# Attiny85VUSB.net
KiCad netlist of a schematic drawn in EAGLE
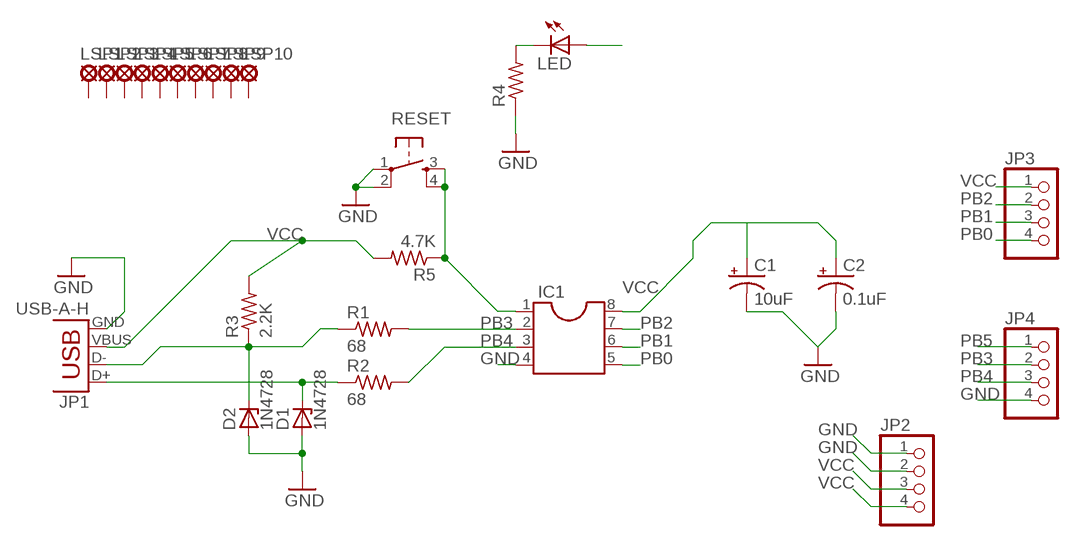
[diagram p0: schematic, sheet 1]

(export (version "E")
  (design (tool "Eeschema 10.0.6"))
  (components
    (comp (ref "C1")
      (value "10uF")
      (footprint "eagle-import:CPOL-RADIAL-100UF-25V")
      (libsource (lib "eagle-import") (part "CAP_POLPTH1"))
    )
    (comp (ref "C2")
      (value "0.1uF")
      (footprint "eagle-import:CPOL-RADIAL-100UF-25V")
      (libsource (lib "eagle-import") (part "CAP_POLPTH1"))
    )
    (comp (ref "D1")
      (value "1N4728")
      (footprint "eagle-import:DO41Z10")
      (libsource (lib "eagle-import") (part "1N4728"))
    )
    (comp (ref "D2")
      (value "1N4728")
      (footprint "eagle-import:DO41Z10")
      (libsource (lib "eagle-import") (part "1N4728"))
    )
    (comp (ref "IC1")
      (value "ATTINY85TESTS")
      (footprint "eagle-import:SOCKET-08")
      (libsource (lib "eagle-import") (part "ATTINY85TESTS"))
    )
    (comp (ref "JP1")
      (value "USB-A-H")
      (footprint "eagle-import:USB-A-H")
      (libsource (lib "eagle-import") (part "USB-A-H"))
    )
    (comp (ref "JP2")
      (value "PINHD-1X4")
      (footprint "eagle-import:1X04")
      (libsource (lib "eagle-import") (part "PINHD-1X4"))
    )
    (comp (ref "JP3")
      (value "PINHD-1X4")
      (footprint "eagle-import:1X04")
      (libsource (lib "eagle-import") (part "PINHD-1X4"))
    )
    (comp (ref "JP4")
      (value "PINHD-1X4")
      (footprint "eagle-import:1X04")
      (libsource (lib "eagle-import") (part "PINHD-1X4"))
    )
    (comp (ref "LED")
      (value "LED5MM")
      (footprint "eagle-import:LED5MM")
      (libsource (lib "eagle-import") (part "LED5MM"))
    )
    (comp (ref "LSP1")
      (value "MCS08")
      (footprint "eagle-import:MCS08")
      (libsource (lib "eagle-import") (part "MCS08"))
    )
    (comp (ref "LSP2")
      (value "MCS08")
      (footprint "eagle-import:MCS08")
      (libsource (lib "eagle-import") (part "MCS08"))
    )
    (comp (ref "LSP3")
      (value "MCS08")
      (footprint "eagle-import:MCS08")
      (libsource (lib "eagle-import") (part "MCS08"))
    )
    (comp (ref "LSP4")
      (value "MCS08")
      (footprint "eagle-import:MCS08")
      (libsource (lib "eagle-import") (part "MCS08"))
    )
    (comp (ref "LSP5")
      (value "MCS08")
      (footprint "eagle-import:MCS08")
      (libsource (lib "eagle-import") (part "MCS08"))
    )
    (comp (ref "LSP6")
      (value "MCS08")
      (footprint "eagle-import:MCS08")
      (libsource (lib "eagle-import") (part "MCS08"))
    )
    (comp (ref "LSP7")
      (value "MCS08")
      (footprint "eagle-import:MCS08")
      (libsource (lib "eagle-import") (part "MCS08"))
    )
    (comp (ref "LSP8")
      (value "MCS08")
      (footprint "eagle-import:MCS08")
      (libsource (lib "eagle-import") (part "MCS08"))
    )
    (comp (ref "LSP9")
      (value "MCS08")
      (footprint "eagle-import:MCS08")
      (libsource (lib "eagle-import") (part "MCS08"))
    )
    (comp (ref "LSP10")
      (value "MCS08")
      (footprint "eagle-import:MCS08")
      (libsource (lib "eagle-import") (part "MCS08"))
    )
    (comp (ref "R1")
      (value "68")
      (footprint "eagle-import:0207_9")
      (libsource (lib "eagle-import") (part "R-US_0207/9"))
    )
    (comp (ref "R2")
      (value "68")
      (footprint "eagle-import:0207_9")
      (libsource (lib "eagle-import") (part "R-US_0207/9"))
    )
    (comp (ref "R3")
      (value "2.2K")
      (footprint "eagle-import:0207_9")
      (libsource (lib "eagle-import") (part "R-US_0207/9"))
    )
    (comp (ref "R4")
      (value "R-US_0207/9")
      (footprint "eagle-import:0207_9")
      (libsource (lib "eagle-import") (part "R-US_0207/9"))
    )
    (comp (ref "R5")
      (value "4.7K")
      (footprint "eagle-import:0207_9")
      (libsource (lib "eagle-import") (part "R-US_0207/9"))
    )
    (comp (ref "RESET")
      (value "TAC_SWITCHPTH")
      (footprint "eagle-import:TACTILE-PTH")
      (libsource (lib "eagle-import") (part "TAC_SWITCHPTH"))
    )
  )
  (nets
    (net (code "1") (name "/PB0") (class "Default")
      (node (ref "IC1") (pin "5") (pinfunction "PB0MOSI_5") (pintype "passive"))
      (node (ref "JP3") (pin "4") (pinfunction "4_4") (pintype "passive"))
    )
    (net (code "2") (name "/PB1") (class "Default")
      (node (ref "IC1") (pin "6") (pinfunction "PB1_MISO_6") (pintype "passive"))
      (node (ref "JP3") (pin "3") (pinfunction "3_3") (pintype "passive"))
      (node (ref "LED") (pin "A") (pinfunction "A_A") (pintype "passive"))
    )
    (net (code "3") (name "/PB2") (class "Default")
      (node (ref "IC1") (pin "7") (pinfunction "PB2SCK_7") (pintype "passive"))
      (node (ref "JP3") (pin "2") (pinfunction "2_2") (pintype "passive"))
    )
    (net (code "4") (name "/PB3") (class "Default")
      (node (ref "IC1") (pin "2") (pinfunction "PB3_CLKI_2") (pintype "passive"))
      (node (ref "JP4") (pin "2") (pinfunction "2_2") (pintype "passive"))
      (node (ref "R1") (pin "2") (pinfunction "2_2") (pintype "passive"))
    )
    (net (code "5") (name "/PB4") (class "Default")
      (node (ref "IC1") (pin "3") (pinfunction "PB4_CLKO_3") (pintype "passive"))
      (node (ref "JP4") (pin "3") (pinfunction "3_3") (pintype "passive"))
      (node (ref "R2") (pin "2") (pinfunction "2_2") (pintype "passive"))
    )
    (net (code "6") (name "/PB5") (class "Default")
      (node (ref "JP4") (pin "1") (pinfunction "1_1") (pintype "passive"))
    )
    (net (code "7") (name "/VCC") (class "Default")
      (node (ref "C1") (pin "1") (pinfunction "+_1") (pintype "passive"))
      (node (ref "C2") (pin "1") (pinfunction "+_1") (pintype "passive"))
      (node (ref "IC1") (pin "8") (pinfunction "VCC_8") (pintype "passive"))
      (node (ref "JP1") (pin "VBUS") (pinfunction "VBUS_VBUS") (pintype "bidirectional"))
      (node (ref "JP2") (pin "3") (pinfunction "3_3") (pintype "passive"))
      (node (ref "JP2") (pin "4") (pinfunction "4_4") (pintype "passive"))
      (node (ref "JP3") (pin "1") (pinfunction "1_1") (pintype "passive"))
      (node (ref "R3") (pin "2") (pinfunction "2_2") (pintype "passive"))
      (node (ref "R5") (pin "2") (pinfunction "2_2") (pintype "passive"))
    )
    (net (code "8") (name "GND") (class "Default")
      (node (ref "C1") (pin "2") (pinfunction "-_2") (pintype "passive"))
      (node (ref "C2") (pin "2") (pinfunction "-_2") (pintype "passive"))
      (node (ref "D1") (pin "A") (pinfunction "A_A") (pintype "passive"))
      (node (ref "D2") (pin "A") (pinfunction "A_A") (pintype "passive"))
      (node (ref "IC1") (pin "4") (pinfunction "GND_4") (pintype "passive"))
      (node (ref "JP1") (pin "GND") (pinfunction "GND_GND") (pintype "bidirectional"))
      (node (ref "JP2") (pin "1") (pinfunction "1_1") (pintype "passive"))
      (node (ref "JP2") (pin "2") (pinfunction "2_2") (pintype "passive"))
      (node (ref "JP4") (pin "4") (pinfunction "4_4") (pintype "passive"))
      (node (ref "R4") (pin "1") (pinfunction "1_1") (pintype "passive"))
      (node (ref "RESET") (pin "1") (pinfunction "1_1") (pintype "passive"))
      (node (ref "RESET") (pin "2") (pinfunction "2_2") (pintype "passive"))
    )
    (net (code "9") (name "Net-(D1-PadC)") (class "Default")
      (node (ref "D1") (pin "C") (pinfunction "C_C") (pintype "passive"))
      (node (ref "JP1") (pin "D+") (pinfunction "D+_D+") (pintype "bidirectional"))
      (node (ref "R2") (pin "1") (pinfunction "1_1") (pintype "passive"))
    )
    (net (code "10") (name "Net-(D2-PadC)") (class "Default")
      (node (ref "D2") (pin "C") (pinfunction "C_C") (pintype "passive"))
      (node (ref "JP1") (pin "D-") (pinfunction "D-_D-") (pintype "bidirectional"))
      (node (ref "R1") (pin "1") (pinfunction "1_1") (pintype "passive"))
      (node (ref "R3") (pin "1") (pinfunction "1_1") (pintype "passive"))
    )
    (net (code "11") (name "Net-(IC1-PB5_~{RESET})") (class "Default")
      (node (ref "IC1") (pin "1") (pinfunction "PB5_~{RESET}_1") (pintype "passive"))
      (node (ref "R5") (pin "1") (pinfunction "1_1") (pintype "passive"))
      (node (ref "RESET") (pin "3") (pinfunction "3_3") (pintype "passive"))
      (node (ref "RESET") (pin "4") (pinfunction "4_4") (pintype "passive"))
    )
    (net (code "12") (name "Net-(LED-C)") (class "Default")
      (node (ref "LED") (pin "K") (pinfunction "C_K") (pintype "passive"))
      (node (ref "R4") (pin "2") (pinfunction "2_2") (pintype "passive"))
    )
    (net (code "13") (name "unconnected-(LSP1-PadMP)") (class "Default")
      (node (ref "LSP1") (pin "MP") (pinfunction "MP_MP") (pintype "passive"))
    )
    (net (code "14") (name "unconnected-(LSP2-PadMP)") (class "Default")
      (node (ref "LSP2") (pin "MP") (pinfunction "MP_MP") (pintype "passive"))
    )
    (net (code "15") (name "unconnected-(LSP3-PadMP)") (class "Default")
      (node (ref "LSP3") (pin "MP") (pinfunction "MP_MP") (pintype "passive"))
    )
    (net (code "16") (name "unconnected-(LSP4-PadMP)") (class "Default")
      (node (ref "LSP4") (pin "MP") (pinfunction "MP_MP") (pintype "passive"))
    )
    (net (code "17") (name "unconnected-(LSP5-PadMP)") (class "Default")
      (node (ref "LSP5") (pin "MP") (pinfunction "MP_MP") (pintype "passive"))
    )
    (net (code "18") (name "unconnected-(LSP6-PadMP)") (class "Default")
      (node (ref "LSP6") (pin "MP") (pinfunction "MP_MP") (pintype "passive"))
    )
    (net (code "19") (name "unconnected-(LSP7-PadMP)") (class "Default")
      (node (ref "LSP7") (pin "MP") (pinfunction "MP_MP") (pintype "passive"))
    )
    (net (code "20") (name "unconnected-(LSP8-PadMP)") (class "Default")
      (node (ref "LSP8") (pin "MP") (pinfunction "MP_MP") (pintype "passive"))
    )
    (net (code "21") (name "unconnected-(LSP9-PadMP)") (class "Default")
      (node (ref "LSP9") (pin "MP") (pinfunction "MP_MP") (pintype "passive"))
    )
    (net (code "22") (name "unconnected-(LSP10-PadMP)") (class "Default")
      (node (ref "LSP10") (pin "MP") (pinfunction "MP_MP") (pintype "passive"))
    )
  )
)
